# BusBoard.net
KiCad netlist of a schematic drawn in EAGLE
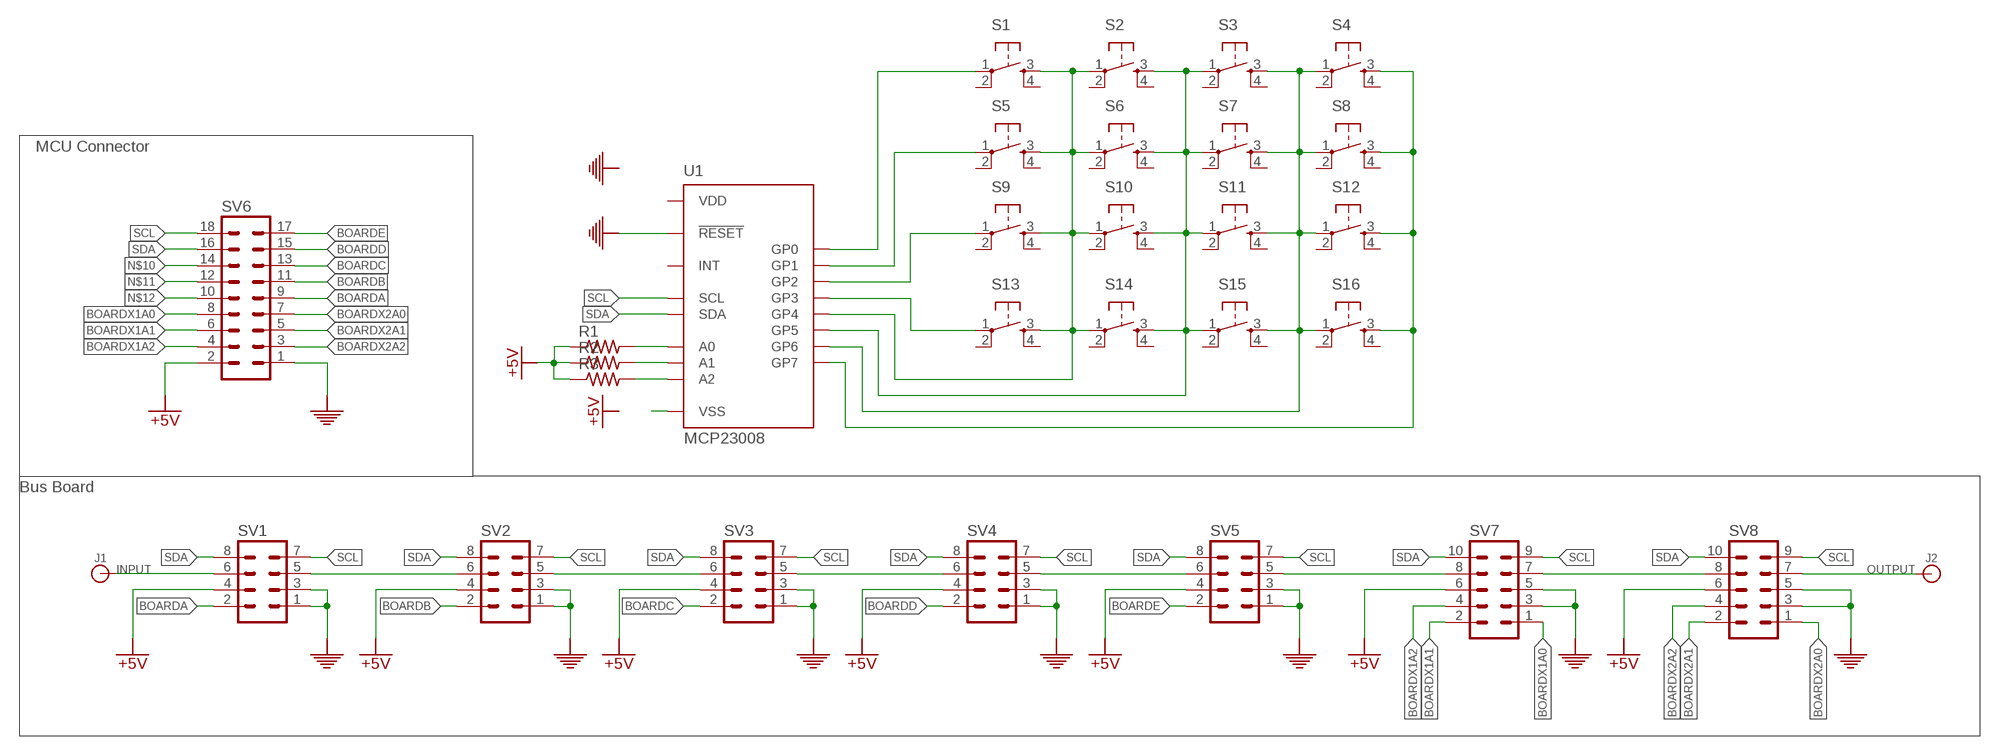
[diagram p0: schematic, sheet 1]

(export (version "E")
  (design (tool "Eeschema 10.0.6"))
  (components
    (comp (ref "J1")
      (value "BANANA_CONN")
      (footprint "eagle-import:BANANA_CONN")
      (libsource (lib "eagle-import") (part "BANANA_CONN"))
    )
    (comp (ref "J2")
      (value "BANANA_CONN")
      (footprint "eagle-import:BANANA_CONN")
      (libsource (lib "eagle-import") (part "BANANA_CONN"))
    )
    (comp (ref "R1")
      (value "R-US_M0805")
      (footprint "eagle-import:M0805")
      (libsource (lib "eagle-import") (part "R-US_M0805"))
    )
    (comp (ref "R2")
      (value "R-US_M0805")
      (footprint "eagle-import:M0805")
      (libsource (lib "eagle-import") (part "R-US_M0805"))
    )
    (comp (ref "R3")
      (value "R-US_M0805")
      (footprint "eagle-import:M0805")
      (libsource (lib "eagle-import") (part "R-US_M0805"))
    )
    (comp (ref "S1")
      (value "TAC_SWITCHPTH")
      (footprint "eagle-import:TACTILE-PTH")
      (libsource (lib "eagle-import") (part "TAC_SWITCHPTH"))
    )
    (comp (ref "S2")
      (value "TAC_SWITCHPTH")
      (footprint "eagle-import:TACTILE-PTH")
      (libsource (lib "eagle-import") (part "TAC_SWITCHPTH"))
    )
    (comp (ref "S3")
      (value "TAC_SWITCHPTH")
      (footprint "eagle-import:TACTILE-PTH")
      (libsource (lib "eagle-import") (part "TAC_SWITCHPTH"))
    )
    (comp (ref "S4")
      (value "TAC_SWITCHPTH")
      (footprint "eagle-import:TACTILE-PTH")
      (libsource (lib "eagle-import") (part "TAC_SWITCHPTH"))
    )
    (comp (ref "S5")
      (value "TAC_SWITCHPTH")
      (footprint "eagle-import:TACTILE-PTH")
      (libsource (lib "eagle-import") (part "TAC_SWITCHPTH"))
    )
    (comp (ref "S6")
      (value "TAC_SWITCHPTH")
      (footprint "eagle-import:TACTILE-PTH")
      (libsource (lib "eagle-import") (part "TAC_SWITCHPTH"))
    )
    (comp (ref "S7")
      (value "TAC_SWITCHPTH")
      (footprint "eagle-import:TACTILE-PTH")
      (libsource (lib "eagle-import") (part "TAC_SWITCHPTH"))
    )
    (comp (ref "S8")
      (value "TAC_SWITCHPTH")
      (footprint "eagle-import:TACTILE-PTH")
      (libsource (lib "eagle-import") (part "TAC_SWITCHPTH"))
    )
    (comp (ref "S9")
      (value "TAC_SWITCHPTH")
      (footprint "eagle-import:TACTILE-PTH")
      (libsource (lib "eagle-import") (part "TAC_SWITCHPTH"))
    )
    (comp (ref "S10")
      (value "TAC_SWITCHPTH")
      (footprint "eagle-import:TACTILE-PTH")
      (libsource (lib "eagle-import") (part "TAC_SWITCHPTH"))
    )
    (comp (ref "S11")
      (value "TAC_SWITCHPTH")
      (footprint "eagle-import:TACTILE-PTH")
      (libsource (lib "eagle-import") (part "TAC_SWITCHPTH"))
    )
    (comp (ref "S12")
      (value "TAC_SWITCHPTH")
      (footprint "eagle-import:TACTILE-PTH")
      (libsource (lib "eagle-import") (part "TAC_SWITCHPTH"))
    )
    (comp (ref "S13")
      (value "TAC_SWITCHPTH")
      (footprint "eagle-import:TACTILE-PTH")
      (libsource (lib "eagle-import") (part "TAC_SWITCHPTH"))
    )
    (comp (ref "S14")
      (value "TAC_SWITCHPTH")
      (footprint "eagle-import:TACTILE-PTH")
      (libsource (lib "eagle-import") (part "TAC_SWITCHPTH"))
    )
    (comp (ref "S15")
      (value "TAC_SWITCHPTH")
      (footprint "eagle-import:TACTILE-PTH")
      (libsource (lib "eagle-import") (part "TAC_SWITCHPTH"))
    )
    (comp (ref "S16")
      (value "TAC_SWITCHPTH")
      (footprint "eagle-import:TACTILE-PTH")
      (libsource (lib "eagle-import") (part "TAC_SWITCHPTH"))
    )
    (comp (ref "SV1")
      (value "MA04-2")
      (footprint "eagle-import:MA04-2")
      (libsource (lib "eagle-import") (part "MA04-2"))
    )
    (comp (ref "SV2")
      (value "MA04-2")
      (footprint "eagle-import:MA04-2")
      (libsource (lib "eagle-import") (part "MA04-2"))
    )
    (comp (ref "SV3")
      (value "MA04-2")
      (footprint "eagle-import:MA04-2")
      (libsource (lib "eagle-import") (part "MA04-2"))
    )
    (comp (ref "SV4")
      (value "MA04-2")
      (footprint "eagle-import:MA04-2")
      (libsource (lib "eagle-import") (part "MA04-2"))
    )
    (comp (ref "SV5")
      (value "MA04-2")
      (footprint "eagle-import:MA04-2")
      (libsource (lib "eagle-import") (part "MA04-2"))
    )
    (comp (ref "SV6")
      (value "MA09-2")
      (footprint "eagle-import:MA09-2")
      (libsource (lib "eagle-import") (part "MA09-2"))
    )
    (comp (ref "SV7")
      (value "MA05-2")
      (footprint "eagle-import:MA05-2")
      (libsource (lib "eagle-import") (part "MA05-2"))
    )
    (comp (ref "SV8")
      (value "MA05-2")
      (footprint "eagle-import:MA05-2")
      (libsource (lib "eagle-import") (part "MA05-2"))
    )
    (comp (ref "U1")
      (value "MCP23008")
      (footprint "eagle-import:SOIC")
      (libsource (lib "eagle-import") (part "MCP23008"))
    )
  )
  (nets
    (net (code "1") (name "+5V") (class "Default")
      (node (ref "R1") (pin "1") (pinfunction "1_1") (pintype "passive"))
      (node (ref "R2") (pin "1") (pinfunction "1_1") (pintype "passive"))
      (node (ref "R3") (pin "1") (pinfunction "1_1") (pintype "passive"))
      (node (ref "SV1") (pin "4") (pinfunction "4_4") (pintype "passive"))
      (node (ref "SV2") (pin "4") (pinfunction "4_4") (pintype "passive"))
      (node (ref "SV3") (pin "4") (pinfunction "4_4") (pintype "passive"))
      (node (ref "SV4") (pin "4") (pinfunction "4_4") (pintype "passive"))
      (node (ref "SV5") (pin "4") (pinfunction "4_4") (pintype "passive"))
      (node (ref "SV6") (pin "2") (pinfunction "2_2") (pintype "passive"))
      (node (ref "SV7") (pin "6") (pinfunction "6_6") (pintype "passive"))
      (node (ref "SV8") (pin "6") (pinfunction "6_6") (pintype "passive"))
    )
    (net (code "2") (name "/INPUT") (class "Default")
      (node (ref "J1") (pin "P$1") (pinfunction "1_P$1") (pintype "passive"))
      (node (ref "SV1") (pin "6") (pinfunction "6_6") (pintype "passive"))
    )
    (net (code "3") (name "/OUTPUT") (class "Default")
      (node (ref "J2") (pin "P$1") (pinfunction "1_P$1") (pintype "passive"))
      (node (ref "SV8") (pin "7") (pinfunction "7_7") (pintype "passive"))
    )
    (net (code "4") (name "/VDD") (class "Default")
      (node (ref "U1") (pin "P$18") (pinfunction "VDD_P$18") (pintype "power_in"))
    )
    (net (code "5") (name "BOARDA") (class "Default")
      (node (ref "SV1") (pin "2") (pinfunction "2_2") (pintype "passive"))
      (node (ref "SV6") (pin "9") (pinfunction "9_9") (pintype "passive"))
    )
    (net (code "6") (name "BOARDB") (class "Default")
      (node (ref "SV2") (pin "2") (pinfunction "2_2") (pintype "passive"))
      (node (ref "SV6") (pin "11") (pinfunction "11_11") (pintype "passive"))
    )
    (net (code "7") (name "BOARDC") (class "Default")
      (node (ref "SV3") (pin "2") (pinfunction "2_2") (pintype "passive"))
      (node (ref "SV6") (pin "13") (pinfunction "13_13") (pintype "passive"))
    )
    (net (code "8") (name "BOARDD") (class "Default")
      (node (ref "SV4") (pin "2") (pinfunction "2_2") (pintype "passive"))
      (node (ref "SV6") (pin "15") (pinfunction "15_15") (pintype "passive"))
    )
    (net (code "9") (name "BOARDE") (class "Default")
      (node (ref "SV5") (pin "2") (pinfunction "2_2") (pintype "passive"))
      (node (ref "SV6") (pin "17") (pinfunction "17_17") (pintype "passive"))
    )
    (net (code "10") (name "BOARDX1A0") (class "Default")
      (node (ref "SV6") (pin "8") (pinfunction "8_8") (pintype "passive"))
      (node (ref "SV7") (pin "1") (pinfunction "1_1") (pintype "passive"))
    )
    (net (code "11") (name "BOARDX1A1") (class "Default")
      (node (ref "SV6") (pin "6") (pinfunction "6_6") (pintype "passive"))
      (node (ref "SV7") (pin "2") (pinfunction "2_2") (pintype "passive"))
    )
    (net (code "12") (name "BOARDX1A2") (class "Default")
      (node (ref "SV6") (pin "4") (pinfunction "4_4") (pintype "passive"))
      (node (ref "SV7") (pin "4") (pinfunction "4_4") (pintype "passive"))
    )
    (net (code "13") (name "BOARDX2A0") (class "Default")
      (node (ref "SV6") (pin "7") (pinfunction "7_7") (pintype "passive"))
      (node (ref "SV8") (pin "1") (pinfunction "1_1") (pintype "passive"))
    )
    (net (code "14") (name "BOARDX2A1") (class "Default")
      (node (ref "SV6") (pin "5") (pinfunction "5_5") (pintype "passive"))
      (node (ref "SV8") (pin "2") (pinfunction "2_2") (pintype "passive"))
    )
    (net (code "15") (name "BOARDX2A2") (class "Default")
      (node (ref "SV6") (pin "3") (pinfunction "3_3") (pintype "passive"))
      (node (ref "SV8") (pin "4") (pinfunction "4_4") (pintype "passive"))
    )
    (net (code "16") (name "GND") (class "Default")
      (node (ref "SV1") (pin "1") (pinfunction "1_1") (pintype "passive"))
      (node (ref "SV1") (pin "3") (pinfunction "3_3") (pintype "passive"))
      (node (ref "SV2") (pin "1") (pinfunction "1_1") (pintype "passive"))
      (node (ref "SV2") (pin "3") (pinfunction "3_3") (pintype "passive"))
      (node (ref "SV3") (pin "1") (pinfunction "1_1") (pintype "passive"))
      (node (ref "SV3") (pin "3") (pinfunction "3_3") (pintype "passive"))
      (node (ref "SV4") (pin "1") (pinfunction "1_1") (pintype "passive"))
      (node (ref "SV4") (pin "3") (pinfunction "3_3") (pintype "passive"))
      (node (ref "SV5") (pin "1") (pinfunction "1_1") (pintype "passive"))
      (node (ref "SV5") (pin "3") (pinfunction "3_3") (pintype "passive"))
      (node (ref "SV6") (pin "1") (pinfunction "1_1") (pintype "passive"))
      (node (ref "SV7") (pin "3") (pinfunction "3_3") (pintype "passive"))
      (node (ref "SV7") (pin "5") (pinfunction "5_5") (pintype "passive"))
      (node (ref "SV8") (pin "3") (pinfunction "3_3") (pintype "passive"))
      (node (ref "SV8") (pin "5") (pinfunction "5_5") (pintype "passive"))
      (node (ref "U1") (pin "P$6") (pinfunction "~{RESET}_P$6") (pintype "input"))
    )
    (net (code "17") (name "N$10") (class "Default")
      (node (ref "SV6") (pin "14") (pinfunction "14_14") (pintype "passive"))
    )
    (net (code "18") (name "N$11") (class "Default")
      (node (ref "SV6") (pin "12") (pinfunction "12_12") (pintype "passive"))
    )
    (net (code "19") (name "N$12") (class "Default")
      (node (ref "SV6") (pin "10") (pinfunction "10_10") (pintype "passive"))
    )
    (net (code "20") (name "Net-(SV1-Pad5)") (class "Default")
      (node (ref "SV1") (pin "5") (pinfunction "5_5") (pintype "passive"))
      (node (ref "SV2") (pin "6") (pinfunction "6_6") (pintype "passive"))
    )
    (net (code "21") (name "Net-(SV2-Pad5)") (class "Default")
      (node (ref "SV2") (pin "5") (pinfunction "5_5") (pintype "passive"))
      (node (ref "SV3") (pin "6") (pinfunction "6_6") (pintype "passive"))
    )
    (net (code "22") (name "Net-(SV3-Pad5)") (class "Default")
      (node (ref "SV3") (pin "5") (pinfunction "5_5") (pintype "passive"))
      (node (ref "SV4") (pin "6") (pinfunction "6_6") (pintype "passive"))
    )
    (net (code "23") (name "Net-(SV4-Pad5)") (class "Default")
      (node (ref "SV4") (pin "5") (pinfunction "5_5") (pintype "passive"))
      (node (ref "SV5") (pin "6") (pinfunction "6_6") (pintype "passive"))
    )
    (net (code "24") (name "Net-(SV5-Pad5)") (class "Default")
      (node (ref "SV5") (pin "5") (pinfunction "5_5") (pintype "passive"))
      (node (ref "SV7") (pin "8") (pinfunction "8_8") (pintype "passive"))
    )
    (net (code "25") (name "Net-(SV7-Pad7)") (class "Default")
      (node (ref "SV7") (pin "7") (pinfunction "7_7") (pintype "passive"))
      (node (ref "SV8") (pin "8") (pinfunction "8_8") (pintype "passive"))
    )
    (net (code "26") (name "Net-(U1-A0)") (class "Default")
      (node (ref "R1") (pin "2") (pinfunction "2_2") (pintype "passive"))
      (node (ref "U1") (pin "P$5") (pinfunction "A0_P$5") (pintype "input"))
    )
    (net (code "27") (name "Net-(U1-A1)") (class "Default")
      (node (ref "R2") (pin "2") (pinfunction "2_2") (pintype "passive"))
      (node (ref "U1") (pin "P$4") (pinfunction "A1_P$4") (pintype "input"))
    )
    (net (code "28") (name "Net-(U1-A2)") (class "Default")
      (node (ref "R3") (pin "2") (pinfunction "2_2") (pintype "passive"))
      (node (ref "U1") (pin "P$3") (pinfunction "A2_P$3") (pintype "input"))
    )
    (net (code "29") (name "Net-(U1-GP0)") (class "Default")
      (node (ref "S1") (pin "1") (pinfunction "1_1") (pintype "passive"))
      (node (ref "U1") (pin "P$10") (pinfunction "GP0_P$10") (pintype "bidirectional"))
    )
    (net (code "30") (name "Net-(U1-GP1)") (class "Default")
      (node (ref "S5") (pin "1") (pinfunction "1_1") (pintype "passive"))
      (node (ref "U1") (pin "P$11") (pinfunction "GP1_P$11") (pintype "bidirectional"))
    )
    (net (code "31") (name "Net-(U1-GP2)") (class "Default")
      (node (ref "S9") (pin "1") (pinfunction "1_1") (pintype "passive"))
      (node (ref "U1") (pin "P$12") (pinfunction "GP2_P$12") (pintype "bidirectional"))
    )
    (net (code "32") (name "Net-(U1-GP3)") (class "Default")
      (node (ref "S13") (pin "1") (pinfunction "1_1") (pintype "passive"))
      (node (ref "U1") (pin "P$13") (pinfunction "GP3_P$13") (pintype "bidirectional"))
    )
    (net (code "33") (name "Net-(U1-GP4)") (class "Default")
      (node (ref "S1") (pin "3") (pinfunction "3_3") (pintype "passive"))
      (node (ref "S10") (pin "1") (pinfunction "1_1") (pintype "passive"))
      (node (ref "S13") (pin "3") (pinfunction "3_3") (pintype "passive"))
      (node (ref "S14") (pin "1") (pinfunction "1_1") (pintype "passive"))
      (node (ref "S2") (pin "1") (pinfunction "1_1") (pintype "passive"))
      (node (ref "S5") (pin "3") (pinfunction "3_3") (pintype "passive"))
      (node (ref "S6") (pin "1") (pinfunction "1_1") (pintype "passive"))
      (node (ref "S9") (pin "3") (pinfunction "3_3") (pintype "passive"))
      (node (ref "U1") (pin "P$14") (pinfunction "GP4_P$14") (pintype "bidirectional"))
    )
    (net (code "34") (name "Net-(U1-GP5)") (class "Default")
      (node (ref "S10") (pin "3") (pinfunction "3_3") (pintype "passive"))
      (node (ref "S11") (pin "1") (pinfunction "1_1") (pintype "passive"))
      (node (ref "S14") (pin "3") (pinfunction "3_3") (pintype "passive"))
      (node (ref "S15") (pin "1") (pinfunction "1_1") (pintype "passive"))
      (node (ref "S2") (pin "3") (pinfunction "3_3") (pintype "passive"))
      (node (ref "S3") (pin "1") (pinfunction "1_1") (pintype "passive"))
      (node (ref "S6") (pin "3") (pinfunction "3_3") (pintype "passive"))
      (node (ref "S7") (pin "1") (pinfunction "1_1") (pintype "passive"))
      (node (ref "U1") (pin "P$15") (pinfunction "GP5_P$15") (pintype "bidirectional"))
    )
    (net (code "35") (name "Net-(U1-GP6)") (class "Default")
      (node (ref "S11") (pin "3") (pinfunction "3_3") (pintype "passive"))
      (node (ref "S12") (pin "1") (pinfunction "1_1") (pintype "passive"))
      (node (ref "S15") (pin "3") (pinfunction "3_3") (pintype "passive"))
      (node (ref "S16") (pin "1") (pinfunction "1_1") (pintype "passive"))
      (node (ref "S3") (pin "3") (pinfunction "3_3") (pintype "passive"))
      (node (ref "S4") (pin "1") (pinfunction "1_1") (pintype "passive"))
      (node (ref "S7") (pin "3") (pinfunction "3_3") (pintype "passive"))
      (node (ref "S8") (pin "1") (pinfunction "1_1") (pintype "passive"))
      (node (ref "U1") (pin "P$16") (pinfunction "GP6_P$16") (pintype "bidirectional"))
    )
    (net (code "36") (name "Net-(U1-GP7)") (class "Default")
      (node (ref "S12") (pin "3") (pinfunction "3_3") (pintype "passive"))
      (node (ref "S16") (pin "3") (pinfunction "3_3") (pintype "passive"))
      (node (ref "S4") (pin "3") (pinfunction "3_3") (pintype "passive"))
      (node (ref "S8") (pin "3") (pinfunction "3_3") (pintype "passive"))
      (node (ref "U1") (pin "P$17") (pinfunction "GP7_P$17") (pintype "bidirectional"))
    )
    (net (code "37") (name "SCL") (class "Default")
      (node (ref "SV1") (pin "7") (pinfunction "7_7") (pintype "passive"))
      (node (ref "SV2") (pin "7") (pinfunction "7_7") (pintype "passive"))
      (node (ref "SV3") (pin "7") (pinfunction "7_7") (pintype "passive"))
      (node (ref "SV4") (pin "7") (pinfunction "7_7") (pintype "passive"))
      (node (ref "SV5") (pin "7") (pinfunction "7_7") (pintype "passive"))
      (node (ref "SV6") (pin "18") (pinfunction "18_18") (pintype "passive"))
      (node (ref "SV7") (pin "9") (pinfunction "9_9") (pintype "passive"))
      (node (ref "SV8") (pin "9") (pinfunction "9_9") (pintype "passive"))
      (node (ref "U1") (pin "P$1") (pinfunction "SCL_P$1") (pintype "input"))
    )
    (net (code "38") (name "SDA") (class "Default")
      (node (ref "SV1") (pin "8") (pinfunction "8_8") (pintype "passive"))
      (node (ref "SV2") (pin "8") (pinfunction "8_8") (pintype "passive"))
      (node (ref "SV3") (pin "8") (pinfunction "8_8") (pintype "passive"))
      (node (ref "SV4") (pin "8") (pinfunction "8_8") (pintype "passive"))
      (node (ref "SV5") (pin "8") (pinfunction "8_8") (pintype "passive"))
      (node (ref "SV6") (pin "16") (pinfunction "16_16") (pintype "passive"))
      (node (ref "SV7") (pin "10") (pinfunction "10_10") (pintype "passive"))
      (node (ref "SV8") (pin "10") (pinfunction "10_10") (pintype "passive"))
      (node (ref "U1") (pin "P$2") (pinfunction "SDA_P$2") (pintype "bidirectional"))
    )
    (net (code "39") (name "unconnected-(S1-Pad2)") (class "Default")
      (node (ref "S1") (pin "2") (pinfunction "2_2") (pintype "passive"))
    )
    (net (code "40") (name "unconnected-(S1-Pad4)") (class "Default")
      (node (ref "S1") (pin "4") (pinfunction "4_4") (pintype "passive"))
    )
    (net (code "41") (name "unconnected-(S2-Pad2)") (class "Default")
      (node (ref "S2") (pin "2") (pinfunction "2_2") (pintype "passive"))
    )
    (net (code "42") (name "unconnected-(S2-Pad4)") (class "Default")
      (node (ref "S2") (pin "4") (pinfunction "4_4") (pintype "passive"))
    )
    (net (code "43") (name "unconnected-(S3-Pad2)") (class "Default")
      (node (ref "S3") (pin "2") (pinfunction "2_2") (pintype "passive"))
    )
    (net (code "44") (name "unconnected-(S3-Pad4)") (class "Default")
      (node (ref "S3") (pin "4") (pinfunction "4_4") (pintype "passive"))
    )
    (net (code "45") (name "unconnected-(S4-Pad2)") (class "Default")
      (node (ref "S4") (pin "2") (pinfunction "2_2") (pintype "passive"))
    )
    (net (code "46") (name "unconnected-(S4-Pad4)") (class "Default")
      (node (ref "S4") (pin "4") (pinfunction "4_4") (pintype "passive"))
    )
    (net (code "47") (name "unconnected-(S5-Pad2)") (class "Default")
      (node (ref "S5") (pin "2") (pinfunction "2_2") (pintype "passive"))
    )
    (net (code "48") (name "unconnected-(S5-Pad4)") (class "Default")
      (node (ref "S5") (pin "4") (pinfunction "4_4") (pintype "passive"))
    )
    (net (code "49") (name "unconnected-(S6-Pad2)") (class "Default")
      (node (ref "S6") (pin "2") (pinfunction "2_2") (pintype "passive"))
    )
    (net (code "50") (name "unconnected-(S6-Pad4)") (class "Default")
      (node (ref "S6") (pin "4") (pinfunction "4_4") (pintype "passive"))
    )
    (net (code "51") (name "unconnected-(S7-Pad2)") (class "Default")
      (node (ref "S7") (pin "2") (pinfunction "2_2") (pintype "passive"))
    )
    (net (code "52") (name "unconnected-(S7-Pad4)") (class "Default")
      (node (ref "S7") (pin "4") (pinfunction "4_4") (pintype "passive"))
    )
    (net (code "53") (name "unconnected-(S8-Pad2)") (class "Default")
      (node (ref "S8") (pin "2") (pinfunction "2_2") (pintype "passive"))
    )
    (net (code "54") (name "unconnected-(S8-Pad4)") (class "Default")
      (node (ref "S8") (pin "4") (pinfunction "4_4") (pintype "passive"))
    )
    (net (code "55") (name "unconnected-(S9-Pad2)") (class "Default")
      (node (ref "S9") (pin "2") (pinfunction "2_2") (pintype "passive"))
    )
    (net (code "56") (name "unconnected-(S9-Pad4)") (class "Default")
      (node (ref "S9") (pin "4") (pinfunction "4_4") (pintype "passive"))
    )
    (net (code "57") (name "unconnected-(S10-Pad2)") (class "Default")
      (node (ref "S10") (pin "2") (pinfunction "2_2") (pintype "passive"))
    )
    (net (code "58") (name "unconnected-(S10-Pad4)") (class "Default")
      (node (ref "S10") (pin "4") (pinfunction "4_4") (pintype "passive"))
    )
    (net (code "59") (name "unconnected-(S11-Pad2)") (class "Default")
      (node (ref "S11") (pin "2") (pinfunction "2_2") (pintype "passive"))
    )
    (net (code "60") (name "unconnected-(S11-Pad4)") (class "Default")
      (node (ref "S11") (pin "4") (pinfunction "4_4") (pintype "passive"))
    )
    (net (code "61") (name "unconnected-(S12-Pad2)") (class "Default")
      (node (ref "S12") (pin "2") (pinfunction "2_2") (pintype "passive"))
    )
    (net (code "62") (name "unconnected-(S12-Pad4)") (class "Default")
      (node (ref "S12") (pin "4") (pinfunction "4_4") (pintype "passive"))
    )
    (net (code "63") (name "unconnected-(S13-Pad2)") (class "Default")
      (node (ref "S13") (pin "2") (pinfunction "2_2") (pintype "passive"))
    )
    (net (code "64") (name "unconnected-(S13-Pad4)") (class "Default")
      (node (ref "S13") (pin "4") (pinfunction "4_4") (pintype "passive"))
    )
    (net (code "65") (name "unconnected-(S14-Pad2)") (class "Default")
      (node (ref "S14") (pin "2") (pinfunction "2_2") (pintype "passive"))
    )
    (net (code "66") (name "unconnected-(S14-Pad4)") (class "Default")
      (node (ref "S14") (pin "4") (pinfunction "4_4") (pintype "passive"))
    )
    (net (code "67") (name "unconnected-(S15-Pad2)") (class "Default")
      (node (ref "S15") (pin "2") (pinfunction "2_2") (pintype "passive"))
    )
    (net (code "68") (name "unconnected-(S15-Pad4)") (class "Default")
      (node (ref "S15") (pin "4") (pinfunction "4_4") (pintype "passive"))
    )
    (net (code "69") (name "unconnected-(S16-Pad2)") (class "Default")
      (node (ref "S16") (pin "2") (pinfunction "2_2") (pintype "passive"))
    )
    (net (code "70") (name "unconnected-(S16-Pad4)") (class "Default")
      (node (ref "S16") (pin "4") (pinfunction "4_4") (pintype "passive"))
    )
    (net (code "71") (name "unconnected-(U1-INT-PadP$8)") (class "Default")
      (node (ref "U1") (pin "P$8") (pinfunction "INT_P$8") (pintype "output"))
    )
    (net (code "72") (name "unconnected-(U1-VSS-PadP$9)") (class "Default")
      (node (ref "U1") (pin "P$9") (pinfunction "VSS_P$9") (pintype "power_in"))
    )
  )
)
